# motordriver.net
KiCad netlist of a schematic drawn in EAGLE
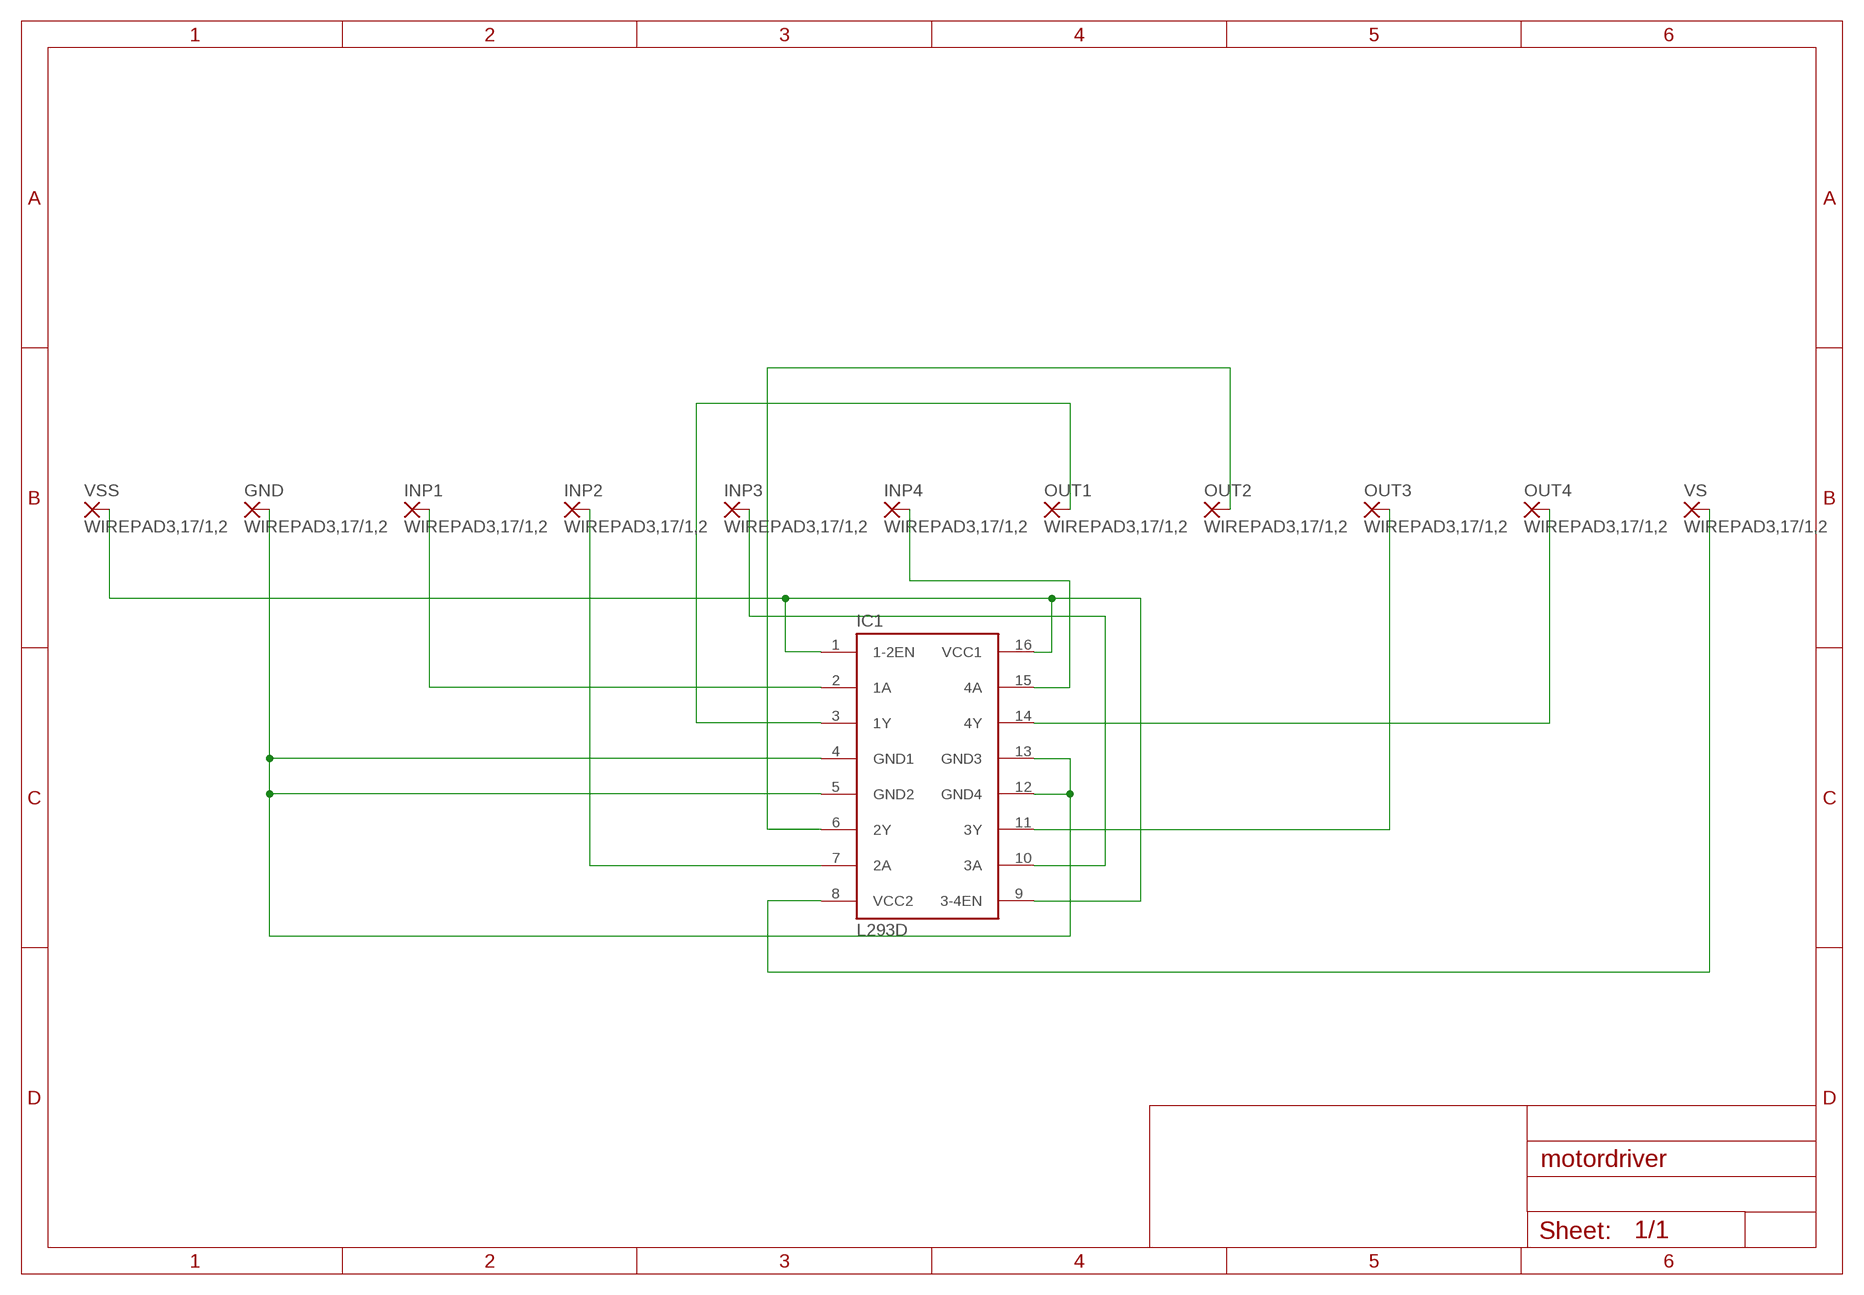
[diagram p0: schematic, sheet 1]

(export (version "E")
  (design (tool "Eeschema 10.0.6"))
  (components
    (comp (ref "GND")
      (value "WIREPAD3,17/1,2")
      (footprint "eagle-import:3,17_1,2")
      (libsource (lib "eagle-import") (part "WIREPAD3,17/1,2"))
    )
    (comp (ref "IC1")
      (value "L293D")
      (footprint "eagle-import:DIL16")
      (libsource (lib "eagle-import") (part "L293D"))
    )
    (comp (ref "INP1")
      (value "WIREPAD3,17/1,2")
      (footprint "eagle-import:3,17_1,2")
      (libsource (lib "eagle-import") (part "WIREPAD3,17/1,2"))
    )
    (comp (ref "INP2")
      (value "WIREPAD3,17/1,2")
      (footprint "eagle-import:3,17_1,2")
      (libsource (lib "eagle-import") (part "WIREPAD3,17/1,2"))
    )
    (comp (ref "INP3")
      (value "WIREPAD3,17/1,2")
      (footprint "eagle-import:3,17_1,2")
      (libsource (lib "eagle-import") (part "WIREPAD3,17/1,2"))
    )
    (comp (ref "INP4")
      (value "WIREPAD3,17/1,2")
      (footprint "eagle-import:3,17_1,2")
      (libsource (lib "eagle-import") (part "WIREPAD3,17/1,2"))
    )
    (comp (ref "OUT1")
      (value "WIREPAD3,17/1,2")
      (footprint "eagle-import:3,17_1,2")
      (libsource (lib "eagle-import") (part "WIREPAD3,17/1,2"))
    )
    (comp (ref "OUT2")
      (value "WIREPAD3,17/1,2")
      (footprint "eagle-import:3,17_1,2")
      (libsource (lib "eagle-import") (part "WIREPAD3,17/1,2"))
    )
    (comp (ref "OUT3")
      (value "WIREPAD3,17/1,2")
      (footprint "eagle-import:3,17_1,2")
      (libsource (lib "eagle-import") (part "WIREPAD3,17/1,2"))
    )
    (comp (ref "OUT4")
      (value "WIREPAD3,17/1,2")
      (footprint "eagle-import:3,17_1,2")
      (libsource (lib "eagle-import") (part "WIREPAD3,17/1,2"))
    )
    (comp (ref "VS")
      (value "WIREPAD3,17/1,2")
      (footprint "eagle-import:3,17_1,2")
      (libsource (lib "eagle-import") (part "WIREPAD3,17/1,2"))
    )
    (comp (ref "VSS")
      (value "WIREPAD3,17/1,2")
      (footprint "eagle-import:3,17_1,2")
      (libsource (lib "eagle-import") (part "WIREPAD3,17/1,2"))
    )
  )
  (nets
    (net (code "1") (name "Net-(GND-P)") (class "Default")
      (node (ref "GND") (pin "1") (pinfunction "P_1") (pintype "passive"))
      (node (ref "IC1") (pin "12") (pinfunction "GND4_12") (pintype "power_in"))
      (node (ref "IC1") (pin "13") (pinfunction "GND3_13") (pintype "power_in"))
      (node (ref "IC1") (pin "4") (pinfunction "GND1_4") (pintype "power_in"))
      (node (ref "IC1") (pin "5") (pinfunction "GND2_5") (pintype "power_in"))
    )
    (net (code "2") (name "Net-(IC1-1-2EN)") (class "Default")
      (node (ref "IC1") (pin "1") (pinfunction "1-2EN_1") (pintype "input"))
      (node (ref "IC1") (pin "16") (pinfunction "VCC1_16") (pintype "power_in"))
      (node (ref "IC1") (pin "9") (pinfunction "3-4EN_9") (pintype "input"))
      (node (ref "VSS") (pin "1") (pinfunction "P_1") (pintype "passive"))
    )
    (net (code "3") (name "Net-(IC1-1A)") (class "Default")
      (node (ref "IC1") (pin "2") (pinfunction "1A_2") (pintype "input"))
      (node (ref "INP1") (pin "1") (pinfunction "P_1") (pintype "passive"))
    )
    (net (code "4") (name "Net-(IC1-1Y)") (class "Default")
      (node (ref "IC1") (pin "3") (pinfunction "1Y_3") (pintype "output"))
      (node (ref "OUT1") (pin "1") (pinfunction "P_1") (pintype "passive"))
    )
    (net (code "5") (name "Net-(IC1-2A)") (class "Default")
      (node (ref "IC1") (pin "7") (pinfunction "2A_7") (pintype "input"))
      (node (ref "INP2") (pin "1") (pinfunction "P_1") (pintype "passive"))
    )
    (net (code "6") (name "Net-(IC1-2Y)") (class "Default")
      (node (ref "IC1") (pin "6") (pinfunction "2Y_6") (pintype "output"))
      (node (ref "OUT2") (pin "1") (pinfunction "P_1") (pintype "passive"))
    )
    (net (code "7") (name "Net-(IC1-3A)") (class "Default")
      (node (ref "IC1") (pin "10") (pinfunction "3A_10") (pintype "input"))
      (node (ref "INP3") (pin "1") (pinfunction "P_1") (pintype "passive"))
    )
    (net (code "8") (name "Net-(IC1-3Y)") (class "Default")
      (node (ref "IC1") (pin "11") (pinfunction "3Y_11") (pintype "output"))
      (node (ref "OUT3") (pin "1") (pinfunction "P_1") (pintype "passive"))
    )
    (net (code "9") (name "Net-(IC1-4A)") (class "Default")
      (node (ref "IC1") (pin "15") (pinfunction "4A_15") (pintype "input"))
      (node (ref "INP4") (pin "1") (pinfunction "P_1") (pintype "passive"))
    )
    (net (code "10") (name "Net-(IC1-4Y)") (class "Default")
      (node (ref "IC1") (pin "14") (pinfunction "4Y_14") (pintype "output"))
      (node (ref "OUT4") (pin "1") (pinfunction "P_1") (pintype "passive"))
    )
    (net (code "11") (name "Net-(IC1-VCC2)") (class "Default")
      (node (ref "IC1") (pin "8") (pinfunction "VCC2_8") (pintype "power_in"))
      (node (ref "VS") (pin "1") (pinfunction "P_1") (pintype "passive"))
    )
  )
)
